# FPGA.net
KiCad netlist of a schematic drawn in Altium Designer
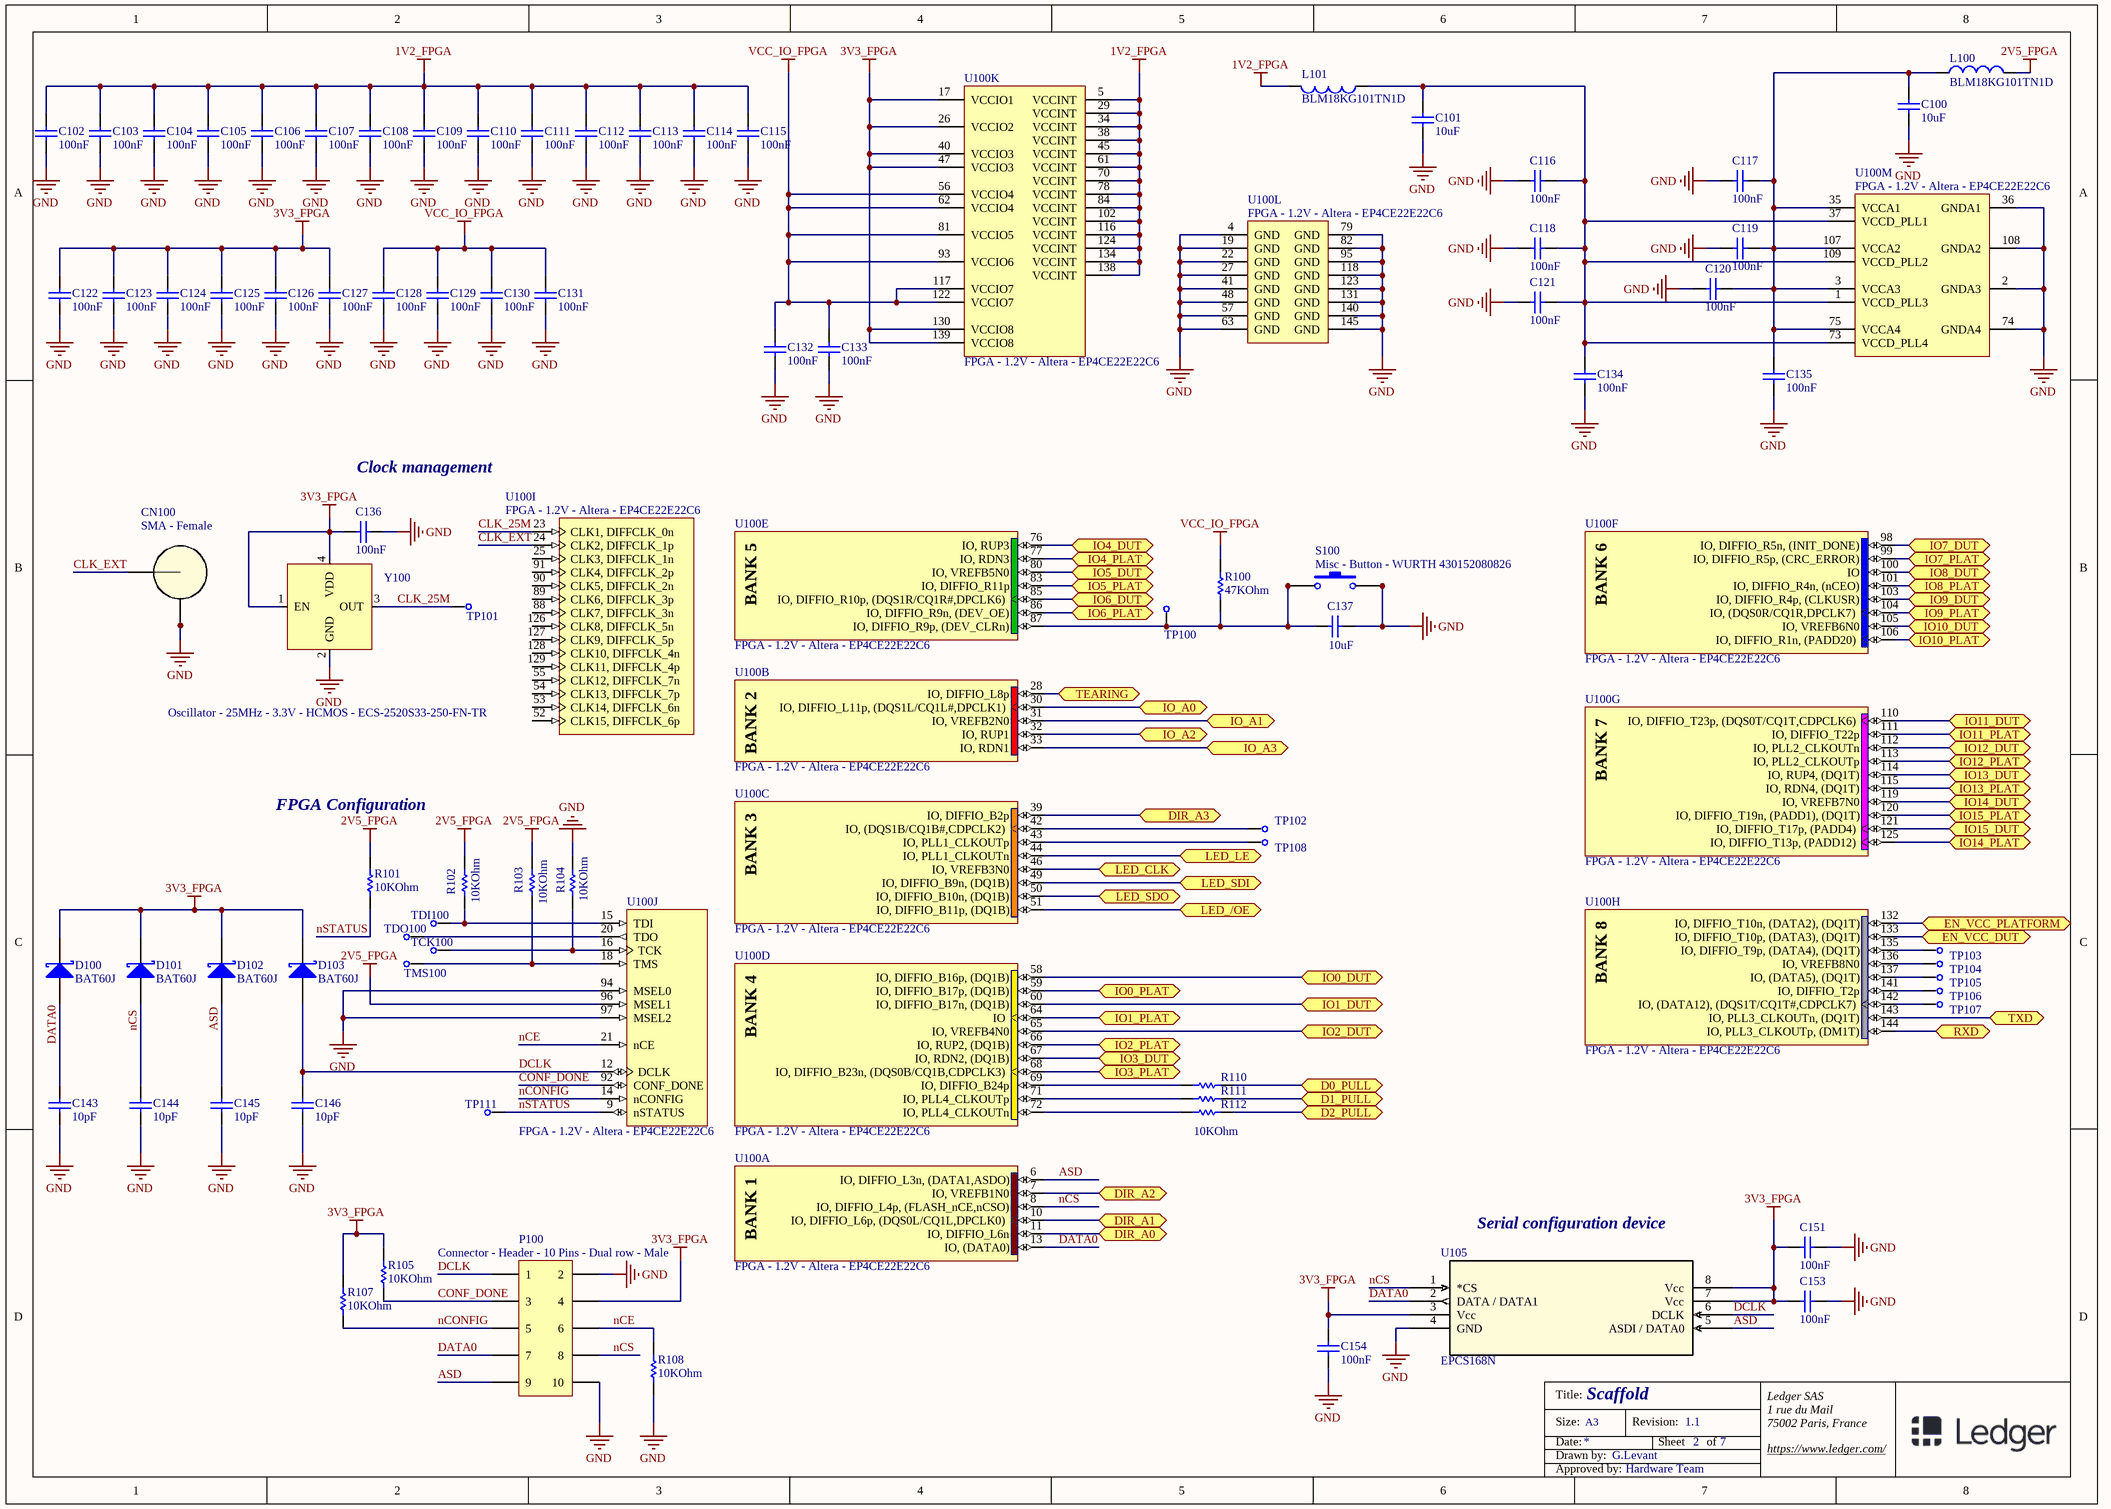
[diagram p0: FPGA.SchDoc]

(export (version "E")
  (design (tool "Eeschema 10.0.6"))
  (components
    (comp (ref "C100")
      (value "10uF")
      (footprint "CAP0603")
      (description "Capacitor 0603 - 10uF - 16V - X5R - 20%")
      (fields (field (name "MANUFACTURER") "Murata") (field (name "TOLERANCE") "20%"))
      (libsource (lib "Ledger_Prod") (part "Capacitor 0603 - 10uF - 16V - X5R - 20%"))
    )
    (comp (ref "C101")
      (value "10uF")
      (footprint "CAP0603")
      (description "Capacitor 0603 - 10uF - 16V - X5R - 20%")
      (fields (field (name "MANUFACTURER") "Murata") (field (name "TOLERANCE") "20%"))
      (libsource (lib "Ledger_Prod") (part "Capacitor 0603 - 10uF - 16V - X5R - 20%"))
    )
    (comp (ref "C102")
      (value "100nF")
      (footprint "CAP0603")
      (description "Capacitor 0603 - 100nF - 16V - X7R - 10%")
      (fields (field (name "POWER") "16V") (field (name "TOLERANCE") "10%"))
      (libsource (lib "Ledger_Prod") (part "Capacitor 0603 - 100nF - 16V - X7R - 10%"))
    )
    (comp (ref "C103")
      (value "100nF")
      (footprint "CAP0603")
      (description "Capacitor 0603 - 100nF - 16V - X7R - 10%")
      (fields (field (name "POWER") "16V") (field (name "TOLERANCE") "10%"))
      (libsource (lib "Ledger_Prod") (part "Capacitor 0603 - 100nF - 16V - X7R - 10%"))
    )
    (comp (ref "C104")
      (value "100nF")
      (footprint "CAP0603")
      (description "Capacitor 0603 - 100nF - 16V - X7R - 10%")
      (fields (field (name "POWER") "16V") (field (name "TOLERANCE") "10%"))
      (libsource (lib "Ledger_Prod") (part "Capacitor 0603 - 100nF - 16V - X7R - 10%"))
    )
    (comp (ref "C105")
      (value "100nF")
      (footprint "CAP0603")
      (description "Capacitor 0603 - 100nF - 16V - X7R - 10%")
      (fields (field (name "POWER") "16V") (field (name "TOLERANCE") "10%"))
      (libsource (lib "Ledger_Prod") (part "Capacitor 0603 - 100nF - 16V - X7R - 10%"))
    )
    (comp (ref "C106")
      (value "100nF")
      (footprint "CAP0603")
      (description "Capacitor 0603 - 100nF - 16V - X7R - 10%")
      (fields (field (name "POWER") "16V") (field (name "TOLERANCE") "10%"))
      (libsource (lib "Ledger_Prod") (part "Capacitor 0603 - 100nF - 16V - X7R - 10%"))
    )
    (comp (ref "C107")
      (value "100nF")
      (footprint "CAP0603")
      (description "Capacitor 0603 - 100nF - 16V - X7R - 10%")
      (fields (field (name "POWER") "16V") (field (name "TOLERANCE") "10%"))
      (libsource (lib "Ledger_Prod") (part "Capacitor 0603 - 100nF - 16V - X7R - 10%"))
    )
    (comp (ref "C108")
      (value "100nF")
      (footprint "CAP0603")
      (description "Capacitor 0603 - 100nF - 16V - X7R - 10%")
      (fields (field (name "POWER") "16V") (field (name "TOLERANCE") "10%"))
      (libsource (lib "Ledger_Prod") (part "Capacitor 0603 - 100nF - 16V - X7R - 10%"))
    )
    (comp (ref "C109")
      (value "100nF")
      (footprint "CAP0603")
      (description "Capacitor 0603 - 100nF - 16V - X7R - 10%")
      (fields (field (name "POWER") "16V") (field (name "TOLERANCE") "10%"))
      (libsource (lib "Ledger_Prod") (part "Capacitor 0603 - 100nF - 16V - X7R - 10%"))
    )
    (comp (ref "C110")
      (value "100nF")
      (footprint "CAP0603")
      (description "Capacitor 0603 - 100nF - 16V - X7R - 10%")
      (fields (field (name "POWER") "16V") (field (name "TOLERANCE") "10%"))
      (libsource (lib "Ledger_Prod") (part "Capacitor 0603 - 100nF - 16V - X7R - 10%"))
    )
    (comp (ref "C111")
      (value "100nF")
      (footprint "CAP0603")
      (description "Capacitor 0603 - 100nF - 16V - X7R - 10%")
      (fields (field (name "POWER") "16V") (field (name "TOLERANCE") "10%"))
      (libsource (lib "Ledger_Prod") (part "Capacitor 0603 - 100nF - 16V - X7R - 10%"))
    )
    (comp (ref "C112")
      (value "100nF")
      (footprint "CAP0603")
      (description "Capacitor 0603 - 100nF - 16V - X7R - 10%")
      (fields (field (name "POWER") "16V") (field (name "TOLERANCE") "10%"))
      (libsource (lib "Ledger_Prod") (part "Capacitor 0603 - 100nF - 16V - X7R - 10%"))
    )
    (comp (ref "C113")
      (value "100nF")
      (footprint "CAP0603")
      (description "Capacitor 0603 - 100nF - 16V - X7R - 10%")
      (fields (field (name "POWER") "16V") (field (name "TOLERANCE") "10%"))
      (libsource (lib "Ledger_Prod") (part "Capacitor 0603 - 100nF - 16V - X7R - 10%"))
    )
    (comp (ref "C114")
      (value "100nF")
      (footprint "CAP0603")
      (description "Capacitor 0603 - 100nF - 16V - X7R - 10%")
      (fields (field (name "POWER") "16V") (field (name "TOLERANCE") "10%"))
      (libsource (lib "Ledger_Prod") (part "Capacitor 0603 - 100nF - 16V - X7R - 10%"))
    )
    (comp (ref "C115")
      (value "100nF")
      (footprint "CAP0603")
      (description "Capacitor 0603 - 100nF - 16V - X7R - 10%")
      (fields (field (name "POWER") "16V") (field (name "TOLERANCE") "10%"))
      (libsource (lib "Ledger_Prod") (part "Capacitor 0603 - 100nF - 16V - X7R - 10%"))
    )
    (comp (ref "C116")
      (value "100nF")
      (footprint "CAP0603")
      (description "Capacitor 0603 - 100nF - 16V - X7R - 10%")
      (fields (field (name "POWER") "16V") (field (name "TOLERANCE") "10%"))
      (libsource (lib "Ledger_Prod") (part "Capacitor 0603 - 100nF - 16V - X7R - 10%"))
    )
    (comp (ref "C117")
      (value "100nF")
      (footprint "CAP0603")
      (description "Capacitor 0603 - 100nF - 16V - X7R - 10%")
      (fields (field (name "POWER") "16V") (field (name "TOLERANCE") "10%"))
      (libsource (lib "Ledger_Prod") (part "Capacitor 0603 - 100nF - 16V - X7R - 10%"))
    )
    (comp (ref "C118")
      (value "100nF")
      (footprint "CAP0603")
      (description "Capacitor 0603 - 100nF - 16V - X7R - 10%")
      (fields (field (name "POWER") "16V") (field (name "TOLERANCE") "10%"))
      (libsource (lib "Ledger_Prod") (part "Capacitor 0603 - 100nF - 16V - X7R - 10%"))
    )
    (comp (ref "C119")
      (value "100nF")
      (footprint "CAP0603")
      (description "Capacitor 0603 - 100nF - 16V - X7R - 10%")
      (fields (field (name "POWER") "16V") (field (name "TOLERANCE") "10%"))
      (libsource (lib "Ledger_Prod") (part "Capacitor 0603 - 100nF - 16V - X7R - 10%"))
    )
    (comp (ref "C120")
      (value "100nF")
      (footprint "CAP0603")
      (description "Capacitor 0603 - 100nF - 16V - X7R - 10%")
      (fields (field (name "POWER") "16V") (field (name "TOLERANCE") "10%"))
      (libsource (lib "Ledger_Prod") (part "Capacitor 0603 - 100nF - 16V - X7R - 10%"))
    )
    (comp (ref "C121")
      (value "100nF")
      (footprint "CAP0603")
      (description "Capacitor 0603 - 100nF - 16V - X7R - 10%")
      (fields (field (name "POWER") "16V") (field (name "TOLERANCE") "10%"))
      (libsource (lib "Ledger_Prod") (part "Capacitor 0603 - 100nF - 16V - X7R - 10%"))
    )
    (comp (ref "C122")
      (value "100nF")
      (footprint "CAP0603")
      (description "Capacitor 0603 - 100nF - 16V - X7R - 10%")
      (fields (field (name "POWER") "16V") (field (name "TOLERANCE") "10%"))
      (libsource (lib "Ledger_Prod") (part "Capacitor 0603 - 100nF - 16V - X7R - 10%"))
    )
    (comp (ref "C123")
      (value "100nF")
      (footprint "CAP0603")
      (description "Capacitor 0603 - 100nF - 16V - X7R - 10%")
      (fields (field (name "POWER") "16V") (field (name "TOLERANCE") "10%"))
      (libsource (lib "Ledger_Prod") (part "Capacitor 0603 - 100nF - 16V - X7R - 10%"))
    )
    (comp (ref "C124")
      (value "100nF")
      (footprint "CAP0603")
      (description "Capacitor 0603 - 100nF - 16V - X7R - 10%")
      (fields (field (name "POWER") "16V") (field (name "TOLERANCE") "10%"))
      (libsource (lib "Ledger_Prod") (part "Capacitor 0603 - 100nF - 16V - X7R - 10%"))
    )
    (comp (ref "C125")
      (value "100nF")
      (footprint "CAP0603")
      (description "Capacitor 0603 - 100nF - 16V - X7R - 10%")
      (fields (field (name "POWER") "16V") (field (name "TOLERANCE") "10%"))
      (libsource (lib "Ledger_Prod") (part "Capacitor 0603 - 100nF - 16V - X7R - 10%"))
    )
    (comp (ref "C126")
      (value "100nF")
      (footprint "CAP0603")
      (description "Capacitor 0603 - 100nF - 16V - X7R - 10%")
      (fields (field (name "POWER") "16V") (field (name "TOLERANCE") "10%"))
      (libsource (lib "Ledger_Prod") (part "Capacitor 0603 - 100nF - 16V - X7R - 10%"))
    )
    (comp (ref "C127")
      (value "100nF")
      (footprint "CAP0603")
      (description "Capacitor 0603 - 100nF - 16V - X7R - 10%")
      (fields (field (name "POWER") "16V") (field (name "TOLERANCE") "10%"))
      (libsource (lib "Ledger_Prod") (part "Capacitor 0603 - 100nF - 16V - X7R - 10%"))
    )
    (comp (ref "C128")
      (value "100nF")
      (footprint "CAP0603")
      (description "Capacitor 0603 - 100nF - 16V - X7R - 10%")
      (fields (field (name "POWER") "16V") (field (name "TOLERANCE") "10%"))
      (libsource (lib "Ledger_Prod") (part "Capacitor 0603 - 100nF - 16V - X7R - 10%"))
    )
    (comp (ref "C129")
      (value "100nF")
      (footprint "CAP0603")
      (description "Capacitor 0603 - 100nF - 16V - X7R - 10%")
      (fields (field (name "POWER") "16V") (field (name "TOLERANCE") "10%"))
      (libsource (lib "Ledger_Prod") (part "Capacitor 0603 - 100nF - 16V - X7R - 10%"))
    )
    (comp (ref "C130")
      (value "100nF")
      (footprint "CAP0603")
      (description "Capacitor 0603 - 100nF - 16V - X7R - 10%")
      (fields (field (name "POWER") "16V") (field (name "TOLERANCE") "10%"))
      (libsource (lib "Ledger_Prod") (part "Capacitor 0603 - 100nF - 16V - X7R - 10%"))
    )
    (comp (ref "C131")
      (value "100nF")
      (footprint "CAP0603")
      (description "Capacitor 0603 - 100nF - 16V - X7R - 10%")
      (fields (field (name "POWER") "16V") (field (name "TOLERANCE") "10%"))
      (libsource (lib "Ledger_Prod") (part "Capacitor 0603 - 100nF - 16V - X7R - 10%"))
    )
    (comp (ref "C132")
      (value "100nF")
      (footprint "CAP0603")
      (description "Capacitor 0603 - 100nF - 16V - X7R - 10%")
      (fields (field (name "POWER") "16V") (field (name "TOLERANCE") "10%"))
      (libsource (lib "Ledger_Prod") (part "Capacitor 0603 - 100nF - 16V - X7R - 10%"))
    )
    (comp (ref "C133")
      (value "100nF")
      (footprint "CAP0603")
      (description "Capacitor 0603 - 100nF - 16V - X7R - 10%")
      (fields (field (name "POWER") "16V") (field (name "TOLERANCE") "10%"))
      (libsource (lib "Ledger_Prod") (part "Capacitor 0603 - 100nF - 16V - X7R - 10%"))
    )
    (comp (ref "C134")
      (value "100nF")
      (footprint "CAP0603")
      (description "Capacitor 0603 - 100nF - 16V - X7R - 10%")
      (fields (field (name "POWER") "16V") (field (name "TOLERANCE") "10%"))
      (libsource (lib "Ledger_Prod") (part "Capacitor 0603 - 100nF - 16V - X7R - 10%"))
    )
    (comp (ref "C135")
      (value "100nF")
      (footprint "CAP0603")
      (description "Capacitor 0603 - 100nF - 16V - X7R - 10%")
      (fields (field (name "POWER") "16V") (field (name "TOLERANCE") "10%"))
      (libsource (lib "Ledger_Prod") (part "Capacitor 0603 - 100nF - 16V - X7R - 10%"))
    )
    (comp (ref "C136")
      (value "100nF")
      (footprint "CAP0603")
      (description "Capacitor 0603 - 100nF - 16V - X7R - 10%")
      (fields (field (name "MANUFACTURER") "Wurth") (field (name "POWER") "16V"))
      (libsource (lib "Ledger_Prod") (part "Capacitor 0603 - 100nF - 16V - X7R - 10%"))
    )
    (comp (ref "C137")
      (value "10uF")
      (footprint "CAP0603")
      (description "Capacitor 0603 - 10uF - 16V - X5R - 20%")
      (fields (field (name "MANUFACTURER") "Murata") (field (name "TOLERANCE") "20%"))
      (libsource (lib "Ledger_Prod") (part "Capacitor 0603 - 10uF - 16V - X5R - 20%"))
    )
    (comp (ref "C143")
      (value "10pF")
      (footprint "CAP0603")
      (description "Capacitor 0603 -  10pF - 100V - COG - 5%")
      (fields (field (name "MANUFACTURER") "TDK") (field (name "POWER") "100V"))
      (libsource (lib "Ledger_Prod") (part "Capacitor 0603 -  10pF - 100V - COG - 5%"))
    )
    (comp (ref "C144")
      (value "10pF")
      (footprint "CAP0603")
      (description "Capacitor 0603 -  10pF - 100V - COG - 5%")
      (fields (field (name "MANUFACTURER") "TDK") (field (name "POWER") "100V"))
      (libsource (lib "Ledger_Prod") (part "Capacitor 0603 -  10pF - 100V - COG - 5%"))
    )
    (comp (ref "C145")
      (value "10pF")
      (footprint "CAP0603")
      (description "Capacitor 0603 -  10pF - 100V - COG - 5%")
      (fields (field (name "MANUFACTURER") "TDK") (field (name "POWER") "100V"))
      (libsource (lib "Ledger_Prod") (part "Capacitor 0603 -  10pF - 100V - COG - 5%"))
    )
    (comp (ref "C146")
      (value "10pF")
      (footprint "CAP0603")
      (description "Capacitor 0603 -  10pF - 100V - COG - 5%")
      (fields (field (name "MANUFACTURER") "TDK") (field (name "POWER") "100V"))
      (libsource (lib "Ledger_Prod") (part "Capacitor 0603 -  10pF - 100V - COG - 5%"))
    )
    (comp (ref "C151")
      (value "100nF")
      (footprint "CAP0603")
      (description "Capacitor 0603 - 100nF - 16V - X7R - 10%")
      (fields (field (name "POWER") "16V") (field (name "TOLERANCE") "10%"))
      (libsource (lib "Ledger_Prod") (part "Capacitor 0603 - 100nF - 16V - X7R - 10%"))
    )
    (comp (ref "C153")
      (value "100nF")
      (footprint "CAP0603")
      (description "Capacitor 0603 - 100nF - 16V - X7R - 10%")
      (fields (field (name "POWER") "16V") (field (name "TOLERANCE") "10%"))
      (libsource (lib "Ledger_Prod") (part "Capacitor 0603 - 100nF - 16V - X7R - 10%"))
    )
    (comp (ref "C154")
      (value "100nF")
      (footprint "CAP0603")
      (description "Capacitor 0603 - 100nF - 16V - X7R - 10%")
      (fields (field (name "POWER") "16V") (field (name "TOLERANCE") "10%"))
      (libsource (lib "Ledger_Prod") (part "Capacitor 0603 - 100nF - 16V - X7R - 10%"))
    )
    (comp (ref "CN100")
      (value "SMA - Female")
      (footprint "SAMTEC_SMA-J-P-X-ST-EM3")
      (description "Connector - SMA - Female - Horizontal - Mid Mount - Samtec - SMA–J–P–H–ST–EM3")
      (fields (field (name "MANUFACTURER") "Samtec"))
      (libsource (lib "Ledger_Dev") (part "Connector - SMA - Female - Horizontal - Mid Mount - Samtec - SMA–J–P–H–ST–EM3"))
    )
    (comp (ref "D100")
      (value "BAT60J")
      (footprint "SOD323/A")
      (fields (field (name "MANUFACTURER") "STMicroelectronics") (field (name "POWER") "310mW"))
      (libsource (lib "Ledger_Dev") (part "Diode -Schottky -10V - 3 A - SOD−323 - BAT60J"))
    )
    (comp (ref "D101")
      (value "BAT60J")
      (footprint "SOD323/A")
      (fields (field (name "MANUFACTURER") "STMicroelectronics") (field (name "POWER") "310mW"))
      (libsource (lib "Ledger_Dev") (part "Diode -Schottky -10V - 3 A - SOD−323 - BAT60J"))
    )
    (comp (ref "D102")
      (value "BAT60J")
      (footprint "SOD323/A")
      (fields (field (name "MANUFACTURER") "STMicroelectronics") (field (name "POWER") "310mW"))
      (libsource (lib "Ledger_Dev") (part "Diode -Schottky -10V - 3 A - SOD−323 - BAT60J"))
    )
    (comp (ref "D103")
      (value "BAT60J")
      (footprint "SOD323/A")
      (fields (field (name "MANUFACTURER") "STMicroelectronics") (field (name "POWER") "310mW"))
      (libsource (lib "Ledger_Dev") (part "Diode -Schottky -10V - 3 A - SOD−323 - BAT60J"))
    )
    (comp (ref "L100")
      (value "BLM18KG101TN1D")
      (footprint "0603")
      (description "Ferrite - Bead - 0603 BLM18")
      (fields (field (name "MANUFACTURER") "MURATA"))
      (libsource (lib "Ledger_Dev") (part "Ferrite - Bead - 0603 BLM18"))
    )
    (comp (ref "L101")
      (value "BLM18KG101TN1D")
      (footprint "0603")
      (description "Ferrite - Bead - 0603 BLM18")
      (fields (field (name "MANUFACTURER") "MURATA"))
      (libsource (lib "Ledger_Dev") (part "Ferrite - Bead - 0603 BLM18"))
    )
    (comp (ref "P100")
      (value "Connector - Header - 10 Pins - Dual row - Male")
      (footprint "SAMTEC_TSW-105-07-G-D")
      (fields (field (name "MANUFACTURER") "Samtec"))
      (libsource (lib "Ledger_Dev") (part "Connector - Header - 10 Pins - Dual row - Male"))
    )
    (comp (ref "R100")
      (value "47KOhm")
      (footprint "RES0603")
      (description "Resistor 0603 -   47KOhm - 1/10W - 1%")
      (fields (field (name "MANUFACTURER") "YAGEO") (field (name "TOLERANCE") "1%"))
      (libsource (lib "Ledger_Prod") (part "Resistor 0603 -   47KOhm - 1/10W - 1%"))
    )
    (comp (ref "R101")
      (value "10KOhm")
      (footprint "RES0603")
      (description "Resistor 0603 -    10KOhm - 1/10W - 1%")
      (fields (field (name "TOLERANCE") "1%") (field (name "POWER") "1/10W"))
      (libsource (lib "Ledger_Prod") (part "Resistor 0603 -    10KOhm - 1/10W - 1%"))
    )
    (comp (ref "R102")
      (value "10KOhm")
      (footprint "RES0603")
      (description "Resistor 0603 -    10KOhm - 1/10W - 1%")
      (fields (field (name "TOLERANCE") "1%") (field (name "POWER") "1/10W"))
      (libsource (lib "Ledger_Prod") (part "Resistor 0603 -    10KOhm - 1/10W - 1%"))
    )
    (comp (ref "R103")
      (value "10KOhm")
      (footprint "RES0603")
      (description "Resistor 0603 -    10KOhm - 1/10W - 1%")
      (fields (field (name "TOLERANCE") "1%") (field (name "POWER") "1/10W"))
      (libsource (lib "Ledger_Prod") (part "Resistor 0603 -    10KOhm - 1/10W - 1%"))
    )
    (comp (ref "R104")
      (value "10KOhm")
      (footprint "RES0603")
      (description "Resistor 0603 -    10KOhm - 1/10W - 1%")
      (fields (field (name "TOLERANCE") "1%") (field (name "POWER") "1/10W"))
      (libsource (lib "Ledger_Prod") (part "Resistor 0603 -    10KOhm - 1/10W - 1%"))
    )
    (comp (ref "R105")
      (value "10KOhm")
      (footprint "RES0603")
      (description "Resistor 0603 -    10KOhm - 1/10W - 1%")
      (fields (field (name "TOLERANCE") "1%") (field (name "POWER") "1/10W"))
      (libsource (lib "Ledger_Prod") (part "Resistor 0603 -    10KOhm - 1/10W - 1%"))
    )
    (comp (ref "R107")
      (value "10KOhm")
      (footprint "RES0603")
      (description "Resistor 0603 -    10KOhm - 1/10W - 1%")
      (fields (field (name "TOLERANCE") "1%") (field (name "POWER") "1/10W"))
      (libsource (lib "Ledger_Prod") (part "Resistor 0603 -    10KOhm - 1/10W - 1%"))
    )
    (comp (ref "R108")
      (value "10KOhm")
      (footprint "RES0603")
      (description "Resistor 0603 -    10KOhm - 1/10W - 1%")
      (fields (field (name "TOLERANCE") "1%") (field (name "POWER") "1/10W"))
      (libsource (lib "Ledger_Prod") (part "Resistor 0603 -    10KOhm - 1/10W - 1%"))
    )
    (comp (ref "R110")
      (value "10KOhm")
      (footprint "RES0603")
      (description "Resistor 0603 -    10KOhm - 1/10W - 1%")
      (fields (field (name "TOLERANCE") "1%") (field (name "POWER") "1/10W"))
      (libsource (lib "Ledger_Prod") (part "Resistor 0603 -    10KOhm - 1/10W - 1%"))
    )
    (comp (ref "R111")
      (value "10KOhm")
      (footprint "RES0603")
      (description "Resistor 0603 -    10KOhm - 1/10W - 1%")
      (fields (field (name "TOLERANCE") "1%") (field (name "POWER") "1/10W"))
      (libsource (lib "Ledger_Prod") (part "Resistor 0603 -    10KOhm - 1/10W - 1%"))
    )
    (comp (ref "R112")
      (value "10KOhm")
      (footprint "RES0603")
      (description "Resistor 0603 -    10KOhm - 1/10W - 1%")
      (fields (field (name "TOLERANCE") "1%") (field (name "POWER") "1/10W"))
      (libsource (lib "Ledger_Prod") (part "Resistor 0603 -    10KOhm - 1/10W - 1%"))
    )
    (comp (ref "S100")
      (value "Misc - Button - WURTH 430152080826")
      (footprint "430152080826")
      (fields (field (name "MANUFACTURER") "Wurth Elektronik"))
      (libsource (lib "Ledger_Prod") (part "Misc - Button - WURTH 430152080826"))
    )
    (comp (ref "TCK100")
      (value "~")
      (footprint "TP_001")
      (description "Misc - Test point CMS")
      (libsource (lib "Ledger_Dev") (part "Misc - Test point CMS"))
    )
    (comp (ref "TDI100")
      (value "~")
      (footprint "TP_001")
      (description "Misc - Test point CMS")
      (libsource (lib "Ledger_Dev") (part "Misc - Test point CMS"))
    )
    (comp (ref "TDO100")
      (value "~")
      (footprint "TP_001")
      (description "Misc - Test point CMS")
      (libsource (lib "Ledger_Dev") (part "Misc - Test point CMS"))
    )
    (comp (ref "TMS100")
      (value "~")
      (footprint "TP_001")
      (description "Misc - Test point CMS")
      (libsource (lib "Ledger_Dev") (part "Misc - Test point CMS"))
    )
    (comp (ref "TP100")
      (value "~")
      (footprint "TP_001")
      (description "Misc - Test point CMS")
      (libsource (lib "Ledger_Dev") (part "Misc - Test point CMS"))
    )
    (comp (ref "TP101")
      (value "~")
      (footprint "TP_001")
      (description "Misc - Test point CMS")
      (libsource (lib "Ledger_Dev") (part "Misc - Test point CMS"))
    )
    (comp (ref "TP102")
      (value "~")
      (footprint "TP_001")
      (description "Misc - Test point CMS")
      (libsource (lib "Ledger_Dev") (part "Misc - Test point CMS"))
    )
    (comp (ref "TP103")
      (value "~")
      (footprint "TP_001")
      (description "Misc - Test point CMS")
      (libsource (lib "Ledger_Dev") (part "Misc - Test point CMS"))
    )
    (comp (ref "TP104")
      (value "~")
      (footprint "TP_001")
      (description "Misc - Test point CMS")
      (libsource (lib "Ledger_Dev") (part "Misc - Test point CMS"))
    )
    (comp (ref "TP105")
      (value "~")
      (footprint "TP_001")
      (description "Misc - Test point CMS")
      (libsource (lib "Ledger_Dev") (part "Misc - Test point CMS"))
    )
    (comp (ref "TP106")
      (value "~")
      (footprint "TP_001")
      (description "Misc - Test point CMS")
      (libsource (lib "Ledger_Dev") (part "Misc - Test point CMS"))
    )
    (comp (ref "TP107")
      (value "~")
      (footprint "TP_001")
      (description "Misc - Test point CMS")
      (libsource (lib "Ledger_Dev") (part "Misc - Test point CMS"))
    )
    (comp (ref "TP108")
      (value "~")
      (footprint "TP_001")
      (description "Misc - Test point CMS")
      (libsource (lib "Ledger_Dev") (part "Misc - Test point CMS"))
    )
    (comp (ref "TP111")
      (value "~")
      (footprint "TP_001")
      (description "Misc - Test point CMS")
      (libsource (lib "Ledger_Dev") (part "Misc - Test point CMS"))
    )
    (comp (ref "U100")
      (value "FPGA - 1.2V - Altera - EP4CE22E22C6")
      (footprint "EQFP144_M")
      (fields (field (name "MANUFACTURER") "Altera"))
      (libsource (lib "Ledger_Dev") (part "FPGA - 1.2V - Altera - EP4CE22E22C6"))
    )
    (comp (ref "U105")
      (value "EPCS168N")
      (footprint "8-SOIC-M")
      (description "IC - Serial configuration device - 16Mbits - SOIC8 - Altera - EPCS168N")
      (fields (field (name "MANUFACTURER") "Altera / Intel"))
      (libsource (lib "Ledger_Dev") (part "IC - Serial configuration device - 16Mbits - SOIC8 - Altera - EPCS168N"))
    )
    (comp (ref "Y100")
      (value "Oscillator - 25MHz - 3.3V - HCMOS - ECS-2520S33-250-FN-TR")
      (footprint "XTAL_2520")
      (fields (field (name "MANUFACTURER") "ECS"))
      (libsource (lib "Ledger_Dev") (part "Oscillator - 25MHz - 3.3V - HCMOS - ECS-2520S33-250-FN-TR"))
    )
  )
  (nets
    (net (code "1") (name "/ASD") (class "Default")
      (node (ref "C145") (pin "2") (pinfunction "2_2") (pintype "passive"))
      (node (ref "D102") (pin "1") (pinfunction "A_1") (pintype "passive"))
      (node (ref "P100") (pin "9") (pinfunction "9_9") (pintype "passive"))
      (node (ref "U100") (pin "6") (pinfunction "IO,_DIFFIO_L3n,_(DATA1,ASDO)_6") (pintype "bidirectional"))
      (node (ref "U105") (pin "5") (pinfunction "ASDI_/_DATA0_5") (pintype "input"))
    )
    (net (code "2") (name "/CLK_25M") (class "Default")
      (node (ref "TP101") (pin "1") (pinfunction "1_1") (pintype "passive"))
      (node (ref "U100") (pin "23") (pinfunction "CLK1,_DIFFCLK_0n_23") (pintype "input"))
      (node (ref "Y100") (pin "3") (pinfunction "OUT_3") (pintype "passive"))
    )
    (net (code "3") (name "/CLK_EXT") (class "Default")
      (node (ref "CN100") (pin "1") (pinfunction "1_1") (pintype "passive"))
      (node (ref "U100") (pin "24") (pinfunction "CLK2,_DIFFCLK_1p_24") (pintype "input"))
    )
    (net (code "4") (name "/CONF_DONE") (class "Default")
      (node (ref "P100") (pin "3") (pinfunction "3_3") (pintype "passive"))
      (node (ref "R105") (pin "1") (pinfunction "1_1") (pintype "passive"))
      (node (ref "U100") (pin "92") (pinfunction "CONF_DONE_92") (pintype "bidirectional"))
    )
    (net (code "5") (name "/D0_PULL") (class "Default")
      (node (ref "R110") (pin "2") (pinfunction "2_2") (pintype "passive"))
    )
    (net (code "6") (name "/D1_PULL") (class "Default")
      (node (ref "R111") (pin "2") (pinfunction "2_2") (pintype "passive"))
    )
    (net (code "7") (name "/D2_PULL") (class "Default")
      (node (ref "R112") (pin "1") (pinfunction "1_1") (pintype "passive"))
    )
    (net (code "8") (name "/DATA0") (class "Default")
      (node (ref "C143") (pin "2") (pinfunction "2_2") (pintype "passive"))
      (node (ref "D100") (pin "1") (pinfunction "A_1") (pintype "passive"))
      (node (ref "P100") (pin "7") (pinfunction "7_7") (pintype "passive"))
      (node (ref "U100") (pin "13") (pinfunction "IO,_(DATA0)_13") (pintype "bidirectional"))
      (node (ref "U105") (pin "2") (pinfunction "DATA_/_DATA1_2") (pintype "output"))
    )
    (net (code "9") (name "/DCLK") (class "Default")
      (node (ref "C146") (pin "2") (pinfunction "2_2") (pintype "passive"))
      (node (ref "D103") (pin "1") (pinfunction "A_1") (pintype "passive"))
      (node (ref "P100") (pin "1") (pinfunction "1_1") (pintype "passive"))
      (node (ref "U100") (pin "12") (pinfunction "DCLK_12") (pintype "bidirectional"))
      (node (ref "U105") (pin "6") (pinfunction "DCLK_6") (pintype "input"))
    )
    (net (code "10") (name "/DIR_A0") (class "Default")
      (node (ref "U100") (pin "11") (pinfunction "IO,_DIFFIO_L6n_11") (pintype "bidirectional"))
    )
    (net (code "11") (name "/DIR_A1") (class "Default")
      (node (ref "U100") (pin "10") (pinfunction "IO,_DIFFIO_L6p,_(DQS0L/CQ1L,DPCLK0)_10") (pintype "bidirectional"))
    )
    (net (code "12") (name "/DIR_A2") (class "Default")
      (node (ref "U100") (pin "7") (pinfunction "IO,_VREFB1N0_7") (pintype "bidirectional"))
    )
    (net (code "13") (name "/DIR_A3") (class "Default")
      (node (ref "U100") (pin "39") (pinfunction "IO,_DIFFIO_B2p_39") (pintype "bidirectional"))
    )
    (net (code "14") (name "/EN_VCC_DUT") (class "Default")
      (node (ref "U100") (pin "133") (pinfunction "IO,_DIFFIO_T10p,_(DATA3),_(DQ1T)_133") (pintype "bidirectional"))
    )
    (net (code "15") (name "/EN_VCC_PLATFORM") (class "Default")
      (node (ref "U100") (pin "132") (pinfunction "IO,_DIFFIO_T10n,_(DATA2),_(DQ1T)_132") (pintype "bidirectional"))
    )
    (net (code "16") (name "/IO0_DUT") (class "Default")
      (node (ref "U100") (pin "58") (pinfunction "IO,_DIFFIO_B16p,_(DQ1B)_58") (pintype "bidirectional"))
    )
    (net (code "17") (name "/IO0_PLAT") (class "Default")
      (node (ref "U100") (pin "59") (pinfunction "IO,_DIFFIO_B17p,_(DQ1B)_59") (pintype "bidirectional"))
    )
    (net (code "18") (name "/IO1_DUT") (class "Default")
      (node (ref "U100") (pin "60") (pinfunction "IO,_DIFFIO_B17n,_(DQ1B)_60") (pintype "bidirectional"))
    )
    (net (code "19") (name "/IO1_PLAT") (class "Default")
      (node (ref "U100") (pin "64") (pinfunction "IO_64") (pintype "bidirectional"))
    )
    (net (code "20") (name "/IO2_DUT") (class "Default")
      (node (ref "U100") (pin "65") (pinfunction "IO,_VREFB4N0_65") (pintype "bidirectional"))
    )
    (net (code "21") (name "/IO2_PLAT") (class "Default")
      (node (ref "U100") (pin "66") (pinfunction "IO,_RUP2,_(DQ1B)_66") (pintype "bidirectional"))
    )
    (net (code "22") (name "/IO3_DUT") (class "Default")
      (node (ref "U100") (pin "67") (pinfunction "IO,_RDN2,_(DQ1B)_67") (pintype "bidirectional"))
    )
    (net (code "23") (name "/IO3_PLAT") (class "Default")
      (node (ref "U100") (pin "68") (pinfunction "IO,_DIFFIO_B23n,_(DQS0B/CQ1B,CDPCLK3)_68") (pintype "bidirectional"))
    )
    (net (code "24") (name "/IO4_DUT") (class "Default")
      (node (ref "U100") (pin "76") (pinfunction "IO,_RUP3_76") (pintype "bidirectional"))
    )
    (net (code "25") (name "/IO4_PLAT") (class "Default")
      (node (ref "U100") (pin "77") (pinfunction "IO,_RDN3_77") (pintype "bidirectional"))
    )
    (net (code "26") (name "/IO5_DUT") (class "Default")
      (node (ref "U100") (pin "80") (pinfunction "IO,_VREFB5N0_80") (pintype "bidirectional"))
    )
    (net (code "27") (name "/IO5_PLAT") (class "Default")
      (node (ref "U100") (pin "83") (pinfunction "IO,_DIFFIO_R11p_83") (pintype "bidirectional"))
    )
    (net (code "28") (name "/IO6_DUT") (class "Default")
      (node (ref "U100") (pin "85") (pinfunction "IO,_DIFFIO_R10p,_(DQS1R/CQ1R#,DPCLK6)_85") (pintype "bidirectional"))
    )
    (net (code "29") (name "/IO6_PLAT") (class "Default")
      (node (ref "U100") (pin "86") (pinfunction "IO,_DIFFIO_R9n,_(DEV_OE)_86") (pintype "bidirectional"))
    )
    (net (code "30") (name "/IO7_DUT") (class "Default")
      (node (ref "U100") (pin "98") (pinfunction "IO,_DIFFIO_R5n,_(INIT_DONE)_98") (pintype "bidirectional"))
    )
    (net (code "31") (name "/IO7_PLAT") (class "Default")
      (node (ref "U100") (pin "99") (pinfunction "IO,_DIFFIO_R5p,_(CRC_ERROR)_99") (pintype "bidirectional"))
    )
    (net (code "32") (name "/IO8_DUT") (class "Default")
      (node (ref "U100") (pin "100") (pinfunction "IO_100") (pintype "bidirectional"))
    )
    (net (code "33") (name "/IO8_PLAT") (class "Default")
      (node (ref "U100") (pin "101") (pinfunction "IO,_DIFFIO_R4n,_(nCEO)_101") (pintype "bidirectional"))
    )
    (net (code "34") (name "/IO9_DUT") (class "Default")
      (node (ref "U100") (pin "103") (pinfunction "IO,_DIFFIO_R4p,_(CLKUSR)_103") (pintype "bidirectional"))
    )
    (net (code "35") (name "/IO9_PLAT") (class "Default")
      (node (ref "U100") (pin "104") (pinfunction "IO,_(DQS0R/CQ1R,DPCLK7)_104") (pintype "bidirectional"))
    )
    (net (code "36") (name "/IO10_DUT") (class "Default")
      (node (ref "U100") (pin "105") (pinfunction "IO,_VREFB6N0_105") (pintype "bidirectional"))
    )
    (net (code "37") (name "/IO10_PLAT") (class "Default")
      (node (ref "U100") (pin "106") (pinfunction "IO,_DIFFIO_R1n,_(PADD20)_106") (pintype "bidirectional"))
    )
    (net (code "38") (name "/IO11_DUT") (class "Default")
      (node (ref "U100") (pin "110") (pinfunction "IO,_DIFFIO_T23p,_(DQS0T/CQ1T,CDPCLK6)_110") (pintype "bidirectional"))
    )
    (net (code "39") (name "/IO11_PLAT") (class "Default")
      (node (ref "U100") (pin "111") (pinfunction "IO,_DIFFIO_T22p_111") (pintype "bidirectional"))
    )
    (net (code "40") (name "/IO12_DUT") (class "Default")
      (node (ref "U100") (pin "112") (pinfunction "IO,_PLL2_CLKOUTn_112") (pintype "bidirectional"))
    )
    (net (code "41") (name "/IO12_PLAT") (class "Default")
      (node (ref "U100") (pin "113") (pinfunction "IO,_PLL2_CLKOUTp_113") (pintype "bidirectional"))
    )
    (net (code "42") (name "/IO13_DUT") (class "Default")
      (node (ref "U100") (pin "114") (pinfunction "IO,_RUP4,_(DQ1T)_114") (pintype "bidirectional"))
    )
    (net (code "43") (name "/IO13_PLAT") (class "Default")
      (node (ref "U100") (pin "115") (pinfunction "IO,_RDN4,_(DQ1T)_115") (pintype "bidirectional"))
    )
    (net (code "44") (name "/IO14_DUT") (class "Default")
      (node (ref "U100") (pin "119") (pinfunction "IO,_VREFB7N0_119") (pintype "bidirectional"))
    )
    (net (code "45") (name "/IO14_PLAT") (class "Default")
      (node (ref "U100") (pin "125") (pinfunction "IO,_DIFFIO_T13p,_(PADD12)_125") (pintype "bidirectional"))
    )
    (net (code "46") (name "/IO15_DUT") (class "Default")
      (node (ref "U100") (pin "121") (pinfunction "IO,_DIFFIO_T17p,_(PADD4)_121") (pintype "bidirectional"))
    )
    (net (code "47") (name "/IO15_PLAT") (class "Default")
      (node (ref "U100") (pin "120") (pinfunction "IO,_DIFFIO_T19n,_(PADD1),_(DQ1T)_120") (pintype "bidirectional"))
    )
    (net (code "48") (name "/IO_A0") (class "Default")
      (node (ref "U100") (pin "30") (pinfunction "IO,_DIFFIO_L11p,_(DQS1L/CQ1L#,DPCLK1)_30") (pintype "bidirectional"))
    )
    (net (code "49") (name "/IO_A1") (class "Default")
      (node (ref "U100") (pin "31") (pinfunction "IO,_VREFB2N0_31") (pintype "bidirectional"))
    )
    (net (code "50") (name "/IO_A2") (class "Default")
      (node (ref "U100") (pin "32") (pinfunction "IO,_RUP1_32") (pintype "bidirectional"))
    )
    (net (code "51") (name "/IO_A3") (class "Default")
      (node (ref "U100") (pin "33") (pinfunction "IO,_RDN1_33") (pintype "bidirectional"))
    )
    (net (code "52") (name "/LED_CLK") (class "Default")
      (node (ref "U100") (pin "46") (pinfunction "IO,_VREFB3N0_46") (pintype "bidirectional"))
    )
    (net (code "53") (name "/LED_LE") (class "Default")
      (node (ref "U100") (pin "44") (pinfunction "IO,_PLL1_CLKOUTn_44") (pintype "bidirectional"))
    )
    (net (code "54") (name "/LED_SDI") (class "Default")
      (node (ref "U100") (pin "49") (pinfunction "IO,_DIFFIO_B9n,_(DQ1B)_49") (pintype "bidirectional"))
    )
    (net (code "55") (name "/LED_SDO") (class "Default")
      (node (ref "U100") (pin "50") (pinfunction "IO,_DIFFIO_B10n,_(DQ1B)_50") (pintype "bidirectional"))
    )
    (net (code "56") (name "/LED_{slash}OE") (class "Default")
      (node (ref "U100") (pin "51") (pinfunction "IO,_DIFFIO_B11p,_(DQ1B)_51") (pintype "bidirectional"))
    )
    (net (code "57") (name "/RXD") (class "Default")
      (node (ref "U100") (pin "144") (pinfunction "IO,_PLL3_CLKOUTp,_(DM1T)_144") (pintype "bidirectional"))
    )
    (net (code "58") (name "/TEARING") (class "Default")
      (node (ref "U100") (pin "28") (pinfunction "IO,_DIFFIO_L8p_28") (pintype "bidirectional"))
    )
    (net (code "59") (name "/TXD") (class "Default")
      (node (ref "U100") (pin "143") (pinfunction "IO,_PLL3_CLKOUTn,_(DQ1T)_143") (pintype "bidirectional"))
    )
    (net (code "60") (name "/nCE") (class "Default")
      (node (ref "P100") (pin "6") (pinfunction "6_6") (pintype "passive"))
      (node (ref "R108") (pin "2") (pinfunction "2_2") (pintype "passive"))
      (node (ref "U100") (pin "21") (pinfunction "nCE_21") (pintype "input"))
    )
    (net (code "61") (name "/nCONFIG") (class "Default")
      (node (ref "P100") (pin "5") (pinfunction "5_5") (pintype "passive"))
      (node (ref "R107") (pin "1") (pinfunction "1_1") (pintype "passive"))
      (node (ref "U100") (pin "14") (pinfunction "nCONFIG_14") (pintype "input"))
    )
    (net (code "62") (name "/nCS") (class "Default")
      (node (ref "C144") (pin "2") (pinfunction "2_2") (pintype "passive"))
      (node (ref "D101") (pin "1") (pinfunction "A_1") (pintype "passive"))
      (node (ref "P100") (pin "8") (pinfunction "8_8") (pintype "passive"))
      (node (ref "U100") (pin "8") (pinfunction "IO,_DIFFIO_L4p,_(FLASH_nCE,nCSO)_8") (pintype "bidirectional"))
      (node (ref "U105") (pin "1") (pinfunction "*CS_1") (pintype "input"))
    )
    (net (code "63") (name "/nSTATUS") (class "Default")
      (node (ref "R101") (pin "1") (pinfunction "1_1") (pintype "passive"))
      (node (ref "TP111") (pin "1") (pinfunction "1_1") (pintype "passive"))
      (node (ref "U100") (pin "9") (pinfunction "nSTATUS_9") (pintype "bidirectional"))
    )
    (net (code "64") (name "1V2_FPGA") (class "Default")
      (node (ref "C102") (pin "2") (pinfunction "2_2") (pintype "passive"))
      (node (ref "C103") (pin "2") (pinfunction "2_2") (pintype "passive"))
      (node (ref "C104") (pin "2") (pinfunction "2_2") (pintype "passive"))
      (node (ref "C105") (pin "2") (pinfunction "2_2") (pintype "passive"))
      (node (ref "C106") (pin "2") (pinfunction "2_2") (pintype "passive"))
      (node (ref "C107") (pin "2") (pinfunction "2_2") (pintype "passive"))
      (node (ref "C108") (pin "2") (pinfunction "2_2") (pintype "passive"))
      (node (ref "C109") (pin "2") (pinfunction "2_2") (pintype "passive"))
      (node (ref "C110") (pin "2") (pinfunction "2_2") (pintype "passive"))
      (node (ref "C111") (pin "2") (pinfunction "2_2") (pintype "passive"))
      (node (ref "C112") (pin "2") (pinfunction "2_2") (pintype "passive"))
      (node (ref "C113") (pin "2") (pinfunction "2_2") (pintype "passive"))
      (node (ref "C114") (pin "2") (pinfunction "2_2") (pintype "passive"))
      (node (ref "C115") (pin "2") (pinfunction "2_2") (pintype "passive"))
      (node (ref "L101") (pin "2") (pinfunction "2_2") (pintype "passive"))
      (node (ref "U100") (pin "102") (pinfunction "VCCINT_102") (pintype "power_in"))
      (node (ref "U100") (pin "116") (pinfunction "VCCINT_116") (pintype "power_in"))
      (node (ref "U100") (pin "124") (pinfunction "VCCINT_124") (pintype "power_in"))
      (node (ref "U100") (pin "134") (pinfunction "VCCINT_134") (pintype "power_in"))
      (node (ref "U100") (pin "138") (pinfunction "VCCINT_138") (pintype "power_in"))
      (node (ref "U100") (pin "29") (pinfunction "VCCINT_29") (pintype "power_in"))
      (node (ref "U100") (pin "34") (pinfunction "VCCINT_34") (pintype "power_in"))
      (node (ref "U100") (pin "38") (pinfunction "VCCINT_38") (pintype "power_in"))
      (node (ref "U100") (pin "45") (pinfunction "VCCINT_45") (pintype "power_in"))
      (node (ref "U100") (pin "5") (pinfunction "VCCINT_5") (pintype "power_in"))
      (node (ref "U100") (pin "61") (pinfunction "VCCINT_61") (pintype "power_in"))
      (node (ref "U100") (pin "70") (pinfunction "VCCINT_70") (pintype "power_in"))
      (node (ref "U100") (pin "78") (pinfunction "VCCINT_78") (pintype "power_in"))
      (node (ref "U100") (pin "84") (pinfunction "VCCINT_84") (pintype "power_in"))
    )
    (net (code "65") (name "2V5_FPGA") (class "Default")
      (node (ref "L100") (pin "2") (pinfunction "2_2") (pintype "passive"))
      (node (ref "R101") (pin "2") (pinfunction "2_2") (pintype "passive"))
      (node (ref "R102") (pin "2") (pinfunction "2_2") (pintype "passive"))
      (node (ref "R103") (pin "2") (pinfunction "2_2") (pintype "passive"))
      (node (ref "U100") (pin "96") (pinfunction "MSEL1_96") (pintype "input"))
    )
    (net (code "66") (name "3V3_FPGA") (class "Default")
      (node (ref "C122") (pin "2") (pinfunction "2_2") (pintype "passive"))
      (node (ref "C123") (pin "2") (pinfunction "2_2") (pintype "passive"))
      (node (ref "C124") (pin "2") (pinfunction "2_2") (pintype "passive"))
      (node (ref "C125") (pin "2") (pinfunction "2_2") (pintype "passive"))
      (node (ref "C126") (pin "2") (pinfunction "2_2") (pintype "passive"))
      (node (ref "C127") (pin "2") (pinfunction "2_2") (pintype "passive"))
      (node (ref "C136") (pin "1") (pinfunction "1_1") (pintype "passive"))
      (node (ref "C151") (pin "2") (pinfunction "2_2") (pintype "passive"))
      (node (ref "C153") (pin "2") (pinfunction "2_2") (pintype "passive"))
      (node (ref "C154") (pin "2") (pinfunction "2_2") (pintype "passive"))
      (node (ref "D100") (pin "2") (pinfunction "K_2") (pintype "passive"))
      (node (ref "D101") (pin "2") (pinfunction "K_2") (pintype "passive"))
      (node (ref "D102") (pin "2") (pinfunction "K_2") (pintype "passive"))
      (node (ref "D103") (pin "2") (pinfunction "K_2") (pintype "passive"))
      (node (ref "P100") (pin "4") (pinfunction "4_4") (pintype "passive"))
      (node (ref "R105") (pin "2") (pinfunction "2_2") (pintype "passive"))
      (node (ref "R107") (pin "2") (pinfunction "2_2") (pintype "passive"))
      (node (ref "U100") (pin "130") (pinfunction "VCCIO8_130") (pintype "power_in"))
      (node (ref "U100") (pin "139") (pinfunction "VCCIO8_139") (pintype "power_in"))
      (node (ref "U100") (pin "17") (pinfunction "VCCIO1_17") (pintype "power_in"))
      (node (ref "U100") (pin "26") (pinfunction "VCCIO2_26") (pintype "power_in"))
      (node (ref "U100") (pin "40") (pinfunction "VCCIO3_40") (pintype "power_in"))
      (node (ref "U100") (pin "47") (pinfunction "VCCIO3_47") (pintype "power_in"))
      (node (ref "U105") (pin "3") (pinfunction "Vcc_3") (pintype "power_in"))
      (node (ref "U105") (pin "7") (pinfunction "Vcc_7") (pintype "power_in"))
      (node (ref "U105") (pin "8") (pinfunction "Vcc_8") (pintype "power_in"))
      (node (ref "Y100") (pin "1") (pinfunction "EN_1") (pintype "passive"))
      (node (ref "Y100") (pin "4") (pinfunction "VDD_4") (pintype "passive"))
    )
    (net (code "67") (name "GND") (class "Default")
      (node (ref "C100") (pin "1") (pinfunction "1_1") (pintype "passive"))
      (node (ref "C101") (pin "1") (pinfunction "1_1") (pintype "passive"))
      (node (ref "C102") (pin "1") (pinfunction "1_1") (pintype "passive"))
      (node (ref "C103") (pin "1") (pinfunction "1_1") (pintype "passive"))
      (node (ref "C104") (pin "1") (pinfunction "1_1") (pintype "passive"))
      (node (ref "C105") (pin "1") (pinfunction "1_1") (pintype "passive"))
      (node (ref "C106") (pin "1") (pinfunction "1_1") (pintype "passive"))
      (node (ref "C107") (pin "1") (pinfunction "1_1") (pintype "passive"))
      (node (ref "C108") (pin "1") (pinfunction "1_1") (pintype "passive"))
      (node (ref "C109") (pin "1") (pinfunction "1_1") (pintype "passive"))
      (node (ref "C110") (pin "1") (pinfunction "1_1") (pintype "passive"))
      (node (ref "C111") (pin "1") (pinfunction "1_1") (pintype "passive"))
      (node (ref "C112") (pin "1") (pinfunction "1_1") (pintype "passive"))
      (node (ref "C113") (pin "1") (pinfunction "1_1") (pintype "passive"))
      (node (ref "C114") (pin "1") (pinfunction "1_1") (pintype "passive"))
      (node (ref "C115") (pin "1") (pinfunction "1_1") (pintype "passive"))
      (node (ref "C116") (pin "1") (pinfunction "1_1") (pintype "passive"))
      (node (ref "C117") (pin "1") (pinfunction "1_1") (pintype "passive"))
      (node (ref "C118") (pin "1") (pinfunction "1_1") (pintype "passive"))
      (node (ref "C119") (pin "1") (pinfunction "1_1") (pintype "passive"))
      (node (ref "C120") (pin "1") (pinfunction "1_1") (pintype "passive"))
      (node (ref "C121") (pin "1") (pinfunction "1_1") (pintype "passive"))
      (node (ref "C122") (pin "1") (pinfunction "1_1") (pintype "passive"))
      (node (ref "C123") (pin "1") (pinfunction "1_1") (pintype "passive"))
      (node (ref "C124") (pin "1") (pinfunction "1_1") (pintype "passive"))
      (node (ref "C125") (pin "1") (pinfunction "1_1") (pintype "passive"))
      (node (ref "C126") (pin "1") (pinfunction "1_1") (pintype "passive"))
      (node (ref "C127") (pin "1") (pinfunction "1_1") (pintype "passive"))
      (node (ref "C128") (pin "1") (pinfunction "1_1") (pintype "passive"))
      (node (ref "C129") (pin "1") (pinfunction "1_1") (pintype "passive"))
      (node (ref "C130") (pin "1") (pinfunction "1_1") (pintype "passive"))
      (node (ref "C131") (pin "1") (pinfunction "1_1") (pintype "passive"))
      (node (ref "C132") (pin "1") (pinfunction "1_1") (pintype "passive"))
      (node (ref "C133") (pin "1") (pinfunction "1_1") (pintype "passive"))
      (node (ref "C134") (pin "1") (pinfunction "1_1") (pintype "passive"))
      (node (ref "C135") (pin "1") (pinfunction "1_1") (pintype "passive"))
      (node (ref "C136") (pin "2") (pinfunction "2_2") (pintype "passive"))
      (node (ref "C137") (pin "1") (pinfunction "1_1") (pintype "passive"))
      (node (ref "C143") (pin "1") (pinfunction "1_1") (pintype "passive"))
      (node (ref "C144") (pin "1") (pinfunction "1_1") (pintype "passive"))
      (node (ref "C145") (pin "1") (pinfunction "1_1") (pintype "passive"))
      (node (ref "C146") (pin "1") (pinfunction "1_1") (pintype "passive"))
      (node (ref "C151") (pin "1") (pinfunction "1_1") (pintype "passive"))
      (node (ref "C153") (pin "1") (pinfunction "1_1") (pintype "passive"))
      (node (ref "C154") (pin "1") (pinfunction "1_1") (pintype "passive"))
      (node (ref "CN100") (pin "2") (pinfunction "2_2") (pintype "passive"))
      (node (ref "CN100") (pin "3") (pinfunction "3_3") (pintype "passive"))
      (node (ref "P100") (pin "10") (pinfunction "10_10") (pintype "passive"))
      (node (ref "P100") (pin "2") (pinfunction "2_2") (pintype "passive"))
      (node (ref "R104") (pin "2") (pinfunction "2_2") (pintype "passive"))
      (node (ref "R108") (pin "1") (pinfunction "1_1") (pintype "passive"))
      (node (ref "S100") (pin "2") (pinfunction "2_2") (pintype "passive"))
      (node (ref "S100") (pin "4") (pinfunction "4_4") (pintype "passive"))
      (node (ref "U100") (pin "108") (pinfunction "GNDA2_108") (pintype "power_in"))
      (node (ref "U100") (pin "118") (pinfunction "GND_118") (pintype "power_in"))
      (node (ref "U100") (pin "123") (pinfunction "GND_123") (pintype "power_in"))
      (node (ref "U100") (pin "131") (pinfunction "GND_131") (pintype "power_in"))
      (node (ref "U100") (pin "140") (pinfunction "GND_140") (pintype "power_in"))
      (node (ref "U100") (pin "145") (pinfunction "GND_145") (pintype "power_in"))
      (node (ref "U100") (pin "19") (pinfunction "GND_19") (pintype "power_in"))
      (node (ref "U100") (pin "2") (pinfunction "GNDA3_2") (pintype "power_in"))
      (node (ref "U100") (pin "22") (pinfunction "GND_22") (pintype "power_in"))
      (node (ref "U100") (pin "27") (pinfunction "GND_27") (pintype "power_in"))
      (node (ref "U100") (pin "36") (pinfunction "GNDA1_36") (pintype "power_in"))
      (node (ref "U100") (pin "4") (pinfunction "GND_4") (pintype "power_in"))
      (node (ref "U100") (pin "41") (pinfunction "GND_41") (pintype "power_in"))
      (node (ref "U100") (pin "48") (pinfunction "GND_48") (pintype "power_in"))
      (node (ref "U100") (pin "57") (pinfunction "GND_57") (pintype "power_in"))
      (node (ref "U100") (pin "63") (pinfunction "GND_63") (pintype "power_in"))
      (node (ref "U100") (pin "74") (pinfunction "GNDA4_74") (pintype "power_in"))
      (node (ref "U100") (pin "79") (pinfunction "GND_79") (pintype "power_in"))
      (node (ref "U100") (pin "82") (pinfunction "GND_82") (pintype "power_in"))
      (node (ref "U100") (pin "94") (pinfunction "MSEL0_94") (pintype "input"))
      (node (ref "U100") (pin "95") (pinfunction "GND_95") (pintype "power_in"))
      (node (ref "U100") (pin "97") (pinfunction "MSEL2_97") (pintype "input"))
      (node (ref "U105") (pin "4") (pinfunction "GND_4") (pintype "power_in"))
      (node (ref "Y100") (pin "2") (pinfunction "GND_2") (pintype "passive"))
    )
    (net (code "68") (name "Net-(U100C-IO,_(DQS1B{slash}CQ1B#,CDPCLK2))") (class "Default")
      (node (ref "TP102") (pin "1") (pinfunction "1_1") (pintype "passive"))
      (node (ref "U100") (pin "42") (pinfunction "IO,_(DQS1B/CQ1B#,CDPCLK2)_42") (pintype "bidirectional"))
    )
    (net (code "69") (name "Net-(U100C-IO,_PLL1_CLKOUTp)") (class "Default")
      (node (ref "TP108") (pin "1") (pinfunction "1_1") (pintype "passive"))
      (node (ref "U100") (pin "43") (pinfunction "IO,_PLL1_CLKOUTp_43") (pintype "bidirectional"))
    )
    (net (code "70") (name "Net-(U100D-IO,_DIFFIO_B24p)") (class "Default")
      (node (ref "R110") (pin "1") (pinfunction "1_1") (pintype "passive"))
      (node (ref "U100") (pin "69") (pinfunction "IO,_DIFFIO_B24p_69") (pintype "bidirectional"))
    )
    (net (code "71") (name "Net-(U100D-IO,_PLL4_CLKOUTn)") (class "Default")
      (node (ref "R112") (pin "2") (pinfunction "2_2") (pintype "passive"))
      (node (ref "U100") (pin "72") (pinfunction "IO,_PLL4_CLKOUTn_72") (pintype "bidirectional"))
    )
    (net (code "72") (name "Net-(U100D-IO,_PLL4_CLKOUTp)") (class "Default")
      (node (ref "R111") (pin "1") (pinfunction "1_1") (pintype "passive"))
      (node (ref "U100") (pin "71") (pinfunction "IO,_PLL4_CLKOUTp_71") (pintype "bidirectional"))
    )
    (net (code "73") (name "Net-(U100E-IO,_DIFFIO_R9p,_(DEV_CLRn))") (class "Default")
      (node (ref "C137") (pin "2") (pinfunction "2_2") (pintype "passive"))
      (node (ref "R100") (pin "1") (pinfunction "1_1") (pintype "passive"))
      (node (ref "S100") (pin "1") (pinfunction "1_1") (pintype "passive"))
      (node (ref "S100") (pin "3") (pinfunction "3_3") (pintype "passive"))
      (node (ref "TP100") (pin "1") (pinfunction "1_1") (pintype "passive"))
      (node (ref "U100") (pin "87") (pinfunction "IO,_DIFFIO_R9p,_(DEV_CLRn)_87") (pintype "bidirectional"))
    )
    (net (code "74") (name "Net-(U100H-IO,_(DATA5),_(DQ1T))") (class "Default")
      (node (ref "TP105") (pin "1") (pinfunction "1_1") (pintype "passive"))
      (node (ref "U100") (pin "137") (pinfunction "IO,_(DATA5),_(DQ1T)_137") (pintype "bidirectional"))
    )
    (net (code "75") (name "Net-(U100H-IO,_(DATA12),_(DQS1T{slash}CQ1T#,CDPCLK7))") (class "Default")
      (node (ref "TP107") (pin "1") (pinfunction "1_1") (pintype "passive"))
      (node (ref "U100") (pin "142") (pinfunction "IO,_(DATA12),_(DQS1T/CQ1T#,CDPCLK7)_142") (pintype "bidirectional"))
    )
    (net (code "76") (name "Net-(U100H-IO,_DIFFIO_T2p)") (class "Default")
      (node (ref "TP106") (pin "1") (pinfunction "1_1") (pintype "passive"))
      (node (ref "U100") (pin "141") (pinfunction "IO,_DIFFIO_T2p_141") (pintype "bidirectional"))
    )
    (net (code "77") (name "Net-(U100H-IO,_DIFFIO_T9p,_(DATA4),_(DQ1T))") (class "Default")
      (node (ref "TP103") (pin "1") (pinfunction "1_1") (pintype "passive"))
      (node (ref "U100") (pin "135") (pinfunction "IO,_DIFFIO_T9p,_(DATA4),_(DQ1T)_135") (pintype "bidirectional"))
    )
    (net (code "78") (name "Net-(U100H-IO,_VREFB8N0)") (class "Default")
      (node (ref "TP104") (pin "1") (pinfunction "1_1") (pintype "passive"))
      (node (ref "U100") (pin "136") (pinfunction "IO,_VREFB8N0_136") (pintype "bidirectional"))
    )
    (net (code "79") (name "Net-(U100J-TCK)") (class "Default")
      (node (ref "R104") (pin "1") (pinfunction "1_1") (pintype "passive"))
      (node (ref "TCK100") (pin "1") (pinfunction "1_1") (pintype "passive"))
      (node (ref "U100") (pin "16") (pinfunction "TCK_16") (pintype "input"))
    )
    (net (code "80") (name "Net-(U100J-TDI)") (class "Default")
      (node (ref "R102") (pin "1") (pinfunction "1_1") (pintype "passive"))
      (node (ref "TDI100") (pin "1") (pinfunction "1_1") (pintype "passive"))
      (node (ref "U100") (pin "15") (pinfunction "TDI_15") (pintype "input"))
    )
    (net (code "81") (name "Net-(U100J-TDO)") (class "Default")
      (node (ref "TDO100") (pin "1") (pinfunction "1_1") (pintype "passive"))
      (node (ref "U100") (pin "20") (pinfunction "TDO_20") (pintype "output"))
    )
    (net (code "82") (name "Net-(U100J-TMS)") (class "Default")
      (node (ref "R103") (pin "1") (pinfunction "1_1") (pintype "passive"))
      (node (ref "TMS100") (pin "1") (pinfunction "1_1") (pintype "passive"))
      (node (ref "U100") (pin "18") (pinfunction "TMS_18") (pintype "input"))
    )
    (net (code "83") (name "Net-(U100M-VCCA1)") (class "Default")
      (node (ref "C100") (pin "2") (pinfunction "2_2") (pintype "passive"))
      (node (ref "C117") (pin "2") (pinfunction "2_2") (pintype "passive"))
      (node (ref "C119") (pin "2") (pinfunction "2_2") (pintype "passive"))
      (node (ref "C120") (pin "2") (pinfunction "2_2") (pintype "passive"))
      (node (ref "C135") (pin "2") (pinfunction "2_2") (pintype "passive"))
      (node (ref "L100") (pin "1") (pinfunction "1_1") (pintype "passive"))
      (node (ref "U100") (pin "107") (pinfunction "VCCA2_107") (pintype "power_in"))
      (node (ref "U100") (pin "3") (pinfunction "VCCA3_3") (pintype "power_in"))
      (node (ref "U100") (pin "35") (pinfunction "VCCA1_35") (pintype "power_in"))
      (node (ref "U100") (pin "75") (pinfunction "VCCA4_75") (pintype "power_in"))
    )
    (net (code "84") (name "Net-(U100M-VCCD_PLL1)") (class "Default")
      (node (ref "C101") (pin "2") (pinfunction "2_2") (pintype "passive"))
      (node (ref "C116") (pin "2") (pinfunction "2_2") (pintype "passive"))
      (node (ref "C118") (pin "2") (pinfunction "2_2") (pintype "passive"))
      (node (ref "C121") (pin "2") (pinfunction "2_2") (pintype "passive"))
      (node (ref "C134") (pin "2") (pinfunction "2_2") (pintype "passive"))
      (node (ref "L101") (pin "1") (pinfunction "1_1") (pintype "passive"))
      (node (ref "U100") (pin "1") (pinfunction "VCCD_PLL3_1") (pintype "power_in"))
      (node (ref "U100") (pin "109") (pinfunction "VCCD_PLL2_109") (pintype "power_in"))
      (node (ref "U100") (pin "37") (pinfunction "VCCD_PLL1_37") (pintype "power_in"))
      (node (ref "U100") (pin "73") (pinfunction "VCCD_PLL4_73") (pintype "power_in"))
    )
    (net (code "85") (name "VCC_IO_FPGA") (class "Default")
      (node (ref "C128") (pin "2") (pinfunction "2_2") (pintype "passive"))
      (node (ref "C129") (pin "2") (pinfunction "2_2") (pintype "passive"))
      (node (ref "C130") (pin "2") (pinfunction "2_2") (pintype "passive"))
      (node (ref "C131") (pin "2") (pinfunction "2_2") (pintype "passive"))
      (node (ref "C132") (pin "2") (pinfunction "2_2") (pintype "passive"))
      (node (ref "C133") (pin "2") (pinfunction "2_2") (pintype "passive"))
      (node (ref "R100") (pin "2") (pinfunction "2_2") (pintype "passive"))
      (node (ref "U100") (pin "117") (pinfunction "VCCIO7_117") (pintype "power_in"))
      (node (ref "U100") (pin "122") (pinfunction "VCCIO7_122") (pintype "power_in"))
      (node (ref "U100") (pin "56") (pinfunction "VCCIO4_56") (pintype "power_in"))
      (node (ref "U100") (pin "62") (pinfunction "VCCIO4_62") (pintype "power_in"))
      (node (ref "U100") (pin "81") (pinfunction "VCCIO5_81") (pintype "power_in"))
      (node (ref "U100") (pin "93") (pinfunction "VCCIO6_93") (pintype "power_in"))
    )
    (net (code "86") (name "unconnected-(U100I-CLK3,_DIFFCLK_1n-Pad25)") (class "Default")
      (node (ref "U100") (pin "25") (pinfunction "CLK3,_DIFFCLK_1n_25") (pintype "input"))
    )
    (net (code "87") (name "unconnected-(U100I-CLK4,_DIFFCLK_2p-Pad91)") (class "Default")
      (node (ref "U100") (pin "91") (pinfunction "CLK4,_DIFFCLK_2p_91") (pintype "input"))
    )
    (net (code "88") (name "unconnected-(U100I-CLK5,_DIFFCLK_2n-Pad90)") (class "Default")
      (node (ref "U100") (pin "90") (pinfunction "CLK5,_DIFFCLK_2n_90") (pintype "input"))
    )
    (net (code "89") (name "unconnected-(U100I-CLK6,_DIFFCLK_3p-Pad89)") (class "Default")
      (node (ref "U100") (pin "89") (pinfunction "CLK6,_DIFFCLK_3p_89") (pintype "input"))
    )
    (net (code "90") (name "unconnected-(U100I-CLK7,_DIFFCLK_3n-Pad88)") (class "Default")
      (node (ref "U100") (pin "88") (pinfunction "CLK7,_DIFFCLK_3n_88") (pintype "input"))
    )
    (net (code "91") (name "unconnected-(U100I-CLK8,_DIFFCLK_5n-Pad126)") (class "Default")
      (node (ref "U100") (pin "126") (pinfunction "CLK8,_DIFFCLK_5n_126") (pintype "input"))
    )
    (net (code "92") (name "unconnected-(U100I-CLK9,_DIFFCLK_5p-Pad127)") (class "Default")
      (node (ref "U100") (pin "127") (pinfunction "CLK9,_DIFFCLK_5p_127") (pintype "input"))
    )
    (net (code "93") (name "unconnected-(U100I-CLK10,_DIFFCLK_4n-Pad128)") (class "Default")
      (node (ref "U100") (pin "128") (pinfunction "CLK10,_DIFFCLK_4n_128") (pintype "input"))
    )
    (net (code "94") (name "unconnected-(U100I-CLK11,_DIFFCLK_4p-Pad129)") (class "Default")
      (node (ref "U100") (pin "129") (pinfunction "CLK11,_DIFFCLK_4p_129") (pintype "input"))
    )
    (net (code "95") (name "unconnected-(U100I-CLK12,_DIFFCLK_7n-Pad55)") (class "Default")
      (node (ref "U100") (pin "55") (pinfunction "CLK12,_DIFFCLK_7n_55") (pintype "input"))
    )
    (net (code "96") (name "unconnected-(U100I-CLK13,_DIFFCLK_7p-Pad54)") (class "Default")
      (node (ref "U100") (pin "54") (pinfunction "CLK13,_DIFFCLK_7p_54") (pintype "input"))
    )
    (net (code "97") (name "unconnected-(U100I-CLK14,_DIFFCLK_6n-Pad53)") (class "Default")
      (node (ref "U100") (pin "53") (pinfunction "CLK14,_DIFFCLK_6n_53") (pintype "input"))
    )
    (net (code "98") (name "unconnected-(U100I-CLK15,_DIFFCLK_6p-Pad52)") (class "Default")
      (node (ref "U100") (pin "52") (pinfunction "CLK15,_DIFFCLK_6p_52") (pintype "input"))
    )
  )
)
